# Motor_Driver2.net
KiCad netlist of a schematic drawn in Altium Designer
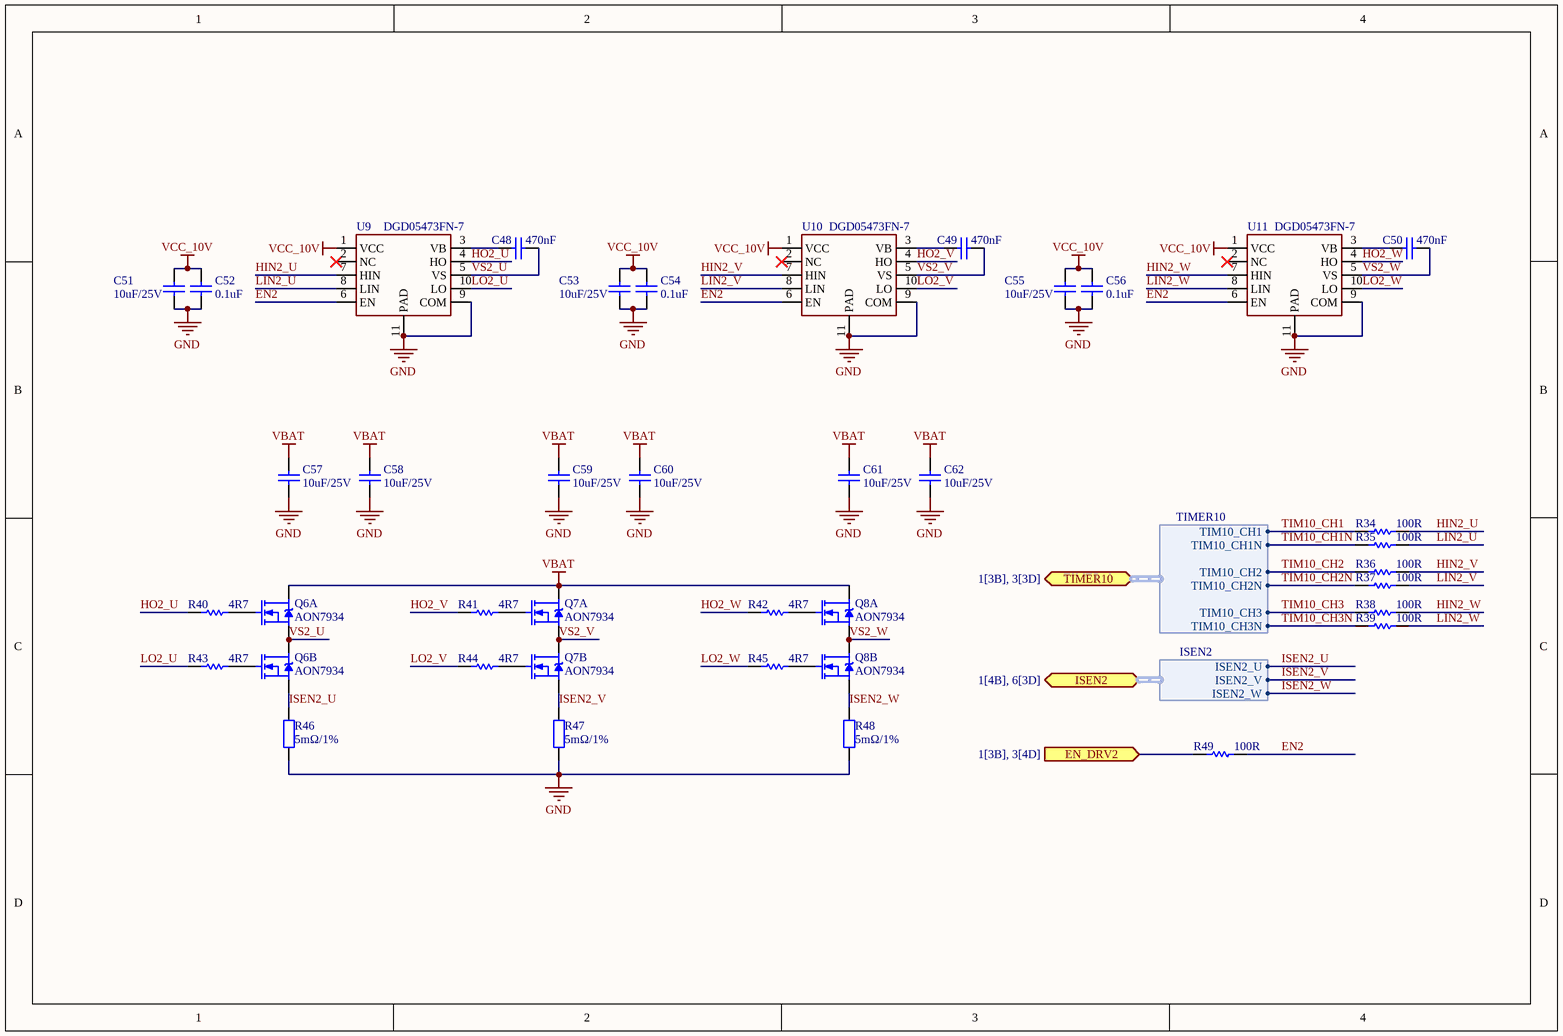
[diagram p0: Motor_Driver2.SchDoc]

(export (version "E")
  (design (tool "Eeschema 10.0.6"))
  (components
    (comp (ref "C48")
      (value "470nF")
      (footprint "C0603_NS")
      (description "Capacitor")
      (fields (field (name "PUBLISHER") "Altium Limited"))
      (libsource (lib "Miscellaneous Devices") (part "Cap"))
    )
    (comp (ref "C49")
      (value "470nF")
      (footprint "C0603_NS")
      (description "Capacitor")
      (fields (field (name "PUBLISHER") "Altium Limited"))
      (libsource (lib "Miscellaneous Devices") (part "Cap"))
    )
    (comp (ref "C50")
      (value "470nF")
      (footprint "C0603_NS")
      (description "Capacitor")
      (fields (field (name "PUBLISHER") "Altium Limited"))
      (libsource (lib "Miscellaneous Devices") (part "Cap"))
    )
    (comp (ref "C51")
      (value "10uF/25V")
      (footprint "C0603_NS")
      (description "Capacitor")
      (fields (field (name "PUBLISHER") "Altium Limited"))
      (libsource (lib "Miscellaneous Devices") (part "Cap"))
    )
    (comp (ref "C52")
      (value "0.1uF")
      (footprint "C0603_NS")
      (description "Capacitor")
      (fields (field (name "PUBLISHER") "Altium Limited"))
      (libsource (lib "Miscellaneous Devices") (part "Cap"))
    )
    (comp (ref "C53")
      (value "10uF/25V")
      (footprint "C0603_NS")
      (description "Capacitor")
      (fields (field (name "PUBLISHER") "Altium Limited"))
      (libsource (lib "Miscellaneous Devices") (part "Cap"))
    )
    (comp (ref "C54")
      (value "0.1uF")
      (footprint "C0603_NS")
      (description "Capacitor")
      (fields (field (name "PUBLISHER") "Altium Limited"))
      (libsource (lib "Miscellaneous Devices") (part "Cap"))
    )
    (comp (ref "C55")
      (value "10uF/25V")
      (footprint "C0603_NS")
      (description "Capacitor")
      (fields (field (name "PUBLISHER") "Altium Limited"))
      (libsource (lib "Miscellaneous Devices") (part "Cap"))
    )
    (comp (ref "C56")
      (value "0.1uF")
      (footprint "C0603_NS")
      (description "Capacitor")
      (fields (field (name "PUBLISHER") "Altium Limited"))
      (libsource (lib "Miscellaneous Devices") (part "Cap"))
    )
    (comp (ref "C57")
      (value "10uF/25V")
      (footprint "C0603_NS")
      (description "Capacitor")
      (libsource (lib "Miscellaneous Devices") (part "Cap"))
    )
    (comp (ref "C58")
      (value "10uF/25V")
      (footprint "C0603_NS")
      (description "Capacitor")
      (libsource (lib "Miscellaneous Devices") (part "Cap"))
    )
    (comp (ref "C59")
      (value "10uF/25V")
      (footprint "C0603_NS")
      (description "Capacitor")
      (libsource (lib "Miscellaneous Devices") (part "Cap"))
    )
    (comp (ref "C60")
      (value "10uF/25V")
      (footprint "C0603_NS")
      (description "Capacitor")
      (libsource (lib "Miscellaneous Devices") (part "Cap"))
    )
    (comp (ref "C61")
      (value "10uF/25V")
      (footprint "C0603_NS")
      (description "Capacitor")
      (libsource (lib "Miscellaneous Devices") (part "Cap"))
    )
    (comp (ref "C62")
      (value "10uF/25V")
      (footprint "C0603_NS")
      (description "Capacitor")
      (libsource (lib "Miscellaneous Devices") (part "Cap"))
    )
    (comp (ref "Q6")
      (value "AON7934")
      (footprint "POWERPAIR_3X3")
      (libsource (lib "my_library") (part "AON7934"))
    )
    (comp (ref "Q7")
      (value "AON7934")
      (footprint "POWERPAIR_3X3")
      (libsource (lib "my_library") (part "AON7934"))
    )
    (comp (ref "Q8")
      (value "AON7934")
      (footprint "POWERPAIR_3X3")
      (libsource (lib "my_library") (part "AON7934"))
    )
    (comp (ref "R34")
      (value "100R")
      (footprint "R0603_NS")
      (description "Resistor")
      (libsource (lib "Miscellaneous Devices") (part "Res1"))
    )
    (comp (ref "R35")
      (value "100R")
      (footprint "R0603_NS")
      (description "Resistor")
      (libsource (lib "Miscellaneous Devices") (part "Res1"))
    )
    (comp (ref "R36")
      (value "100R")
      (footprint "R0603_NS")
      (description "Resistor")
      (libsource (lib "Miscellaneous Devices") (part "Res1"))
    )
    (comp (ref "R37")
      (value "100R")
      (footprint "R0603_NS")
      (description "Resistor")
      (libsource (lib "Miscellaneous Devices") (part "Res1"))
    )
    (comp (ref "R38")
      (value "100R")
      (footprint "R0603_NS")
      (description "Resistor")
      (libsource (lib "Miscellaneous Devices") (part "Res1"))
    )
    (comp (ref "R39")
      (value "100R")
      (footprint "R0603_NS")
      (description "Resistor")
      (libsource (lib "Miscellaneous Devices") (part "Res1"))
    )
    (comp (ref "R40")
      (value "4R7")
      (footprint "R0603_NS")
      (description "Resistor")
      (libsource (lib "Miscellaneous Devices") (part "Res1"))
    )
    (comp (ref "R41")
      (value "4R7")
      (footprint "R0603_NS")
      (description "Resistor")
      (libsource (lib "Miscellaneous Devices") (part "Res1"))
    )
    (comp (ref "R42")
      (value "4R7")
      (footprint "R0603_NS")
      (description "Resistor")
      (libsource (lib "Miscellaneous Devices") (part "Res1"))
    )
    (comp (ref "R43")
      (value "4R7")
      (footprint "R0603_NS")
      (description "Resistor")
      (libsource (lib "Miscellaneous Devices") (part "Res1"))
    )
    (comp (ref "R44")
      (value "4R7")
      (footprint "R0603_NS")
      (description "Resistor")
      (libsource (lib "Miscellaneous Devices") (part "Res1"))
    )
    (comp (ref "R45")
      (value "4R7")
      (footprint "R0603_NS")
      (description "Resistor")
      (libsource (lib "Miscellaneous Devices") (part "Res1"))
    )
    (comp (ref "R46")
      (value "5mΩ/1%")
      (footprint "R1206_NS")
      (description "Resistor")
      (fields (field (name "PUBLISHER") "Altium Limited"))
      (libsource (lib "Miscellaneous Devices") (part "Res2"))
    )
    (comp (ref "R47")
      (value "5mΩ/1%")
      (footprint "R1206_NS")
      (description "Resistor")
      (fields (field (name "PUBLISHER") "Altium Limited"))
      (libsource (lib "Miscellaneous Devices") (part "Res2"))
    )
    (comp (ref "R48")
      (value "5mΩ/1%")
      (footprint "R1206_NS")
      (description "Resistor")
      (fields (field (name "PUBLISHER") "Altium Limited"))
      (libsource (lib "Miscellaneous Devices") (part "Res2"))
    )
    (comp (ref "R49")
      (value "100R")
      (footprint "R0603_NS")
      (description "Resistor")
      (libsource (lib "Miscellaneous Devices") (part "Res1"))
    )
    (comp (ref "U9")
      (value "DGD05473FN-7")
      (footprint "W-DFN3030-10_DGD05473")
      (libsource (lib "my_library") (part "DGD05473"))
    )
    (comp (ref "U10")
      (value "DGD05473FN-7")
      (footprint "W-DFN3030-10_DGD05473")
      (libsource (lib "my_library") (part "DGD05473"))
    )
    (comp (ref "U11")
      (value "DGD05473FN-7")
      (footprint "W-DFN3030-10_DGD05473")
      (libsource (lib "my_library") (part "DGD05473"))
    )
  )
  (nets
    (net (code "3") (name "/EN2") (class "Default")
      (node (ref "R49") (pin "2") (pinfunction "2_2") (pintype "passive"))
      (node (ref "U10") (pin "6") (pinfunction "EN_6") (pintype "passive"))
      (node (ref "U11") (pin "6") (pinfunction "EN_6") (pintype "passive"))
      (node (ref "U9") (pin "6") (pinfunction "EN_6") (pintype "passive"))
    )
    (net (code "4") (name "/EN_DRV2") (class "Default")
      (node (ref "R49") (pin "1") (pinfunction "1_1") (pintype "passive"))
    )
    (net (code "5") (name "/HIN2_U") (class "Default")
      (node (ref "R34") (pin "2") (pinfunction "2_2") (pintype "passive"))
      (node (ref "U9") (pin "7") (pinfunction "HIN_7") (pintype "passive"))
    )
    (net (code "6") (name "/HIN2_V") (class "Default")
      (node (ref "R36") (pin "2") (pinfunction "2_2") (pintype "passive"))
      (node (ref "U10") (pin "7") (pinfunction "HIN_7") (pintype "passive"))
    )
    (net (code "7") (name "/HIN2_W") (class "Default")
      (node (ref "R38") (pin "2") (pinfunction "2_2") (pintype "passive"))
      (node (ref "U11") (pin "7") (pinfunction "HIN_7") (pintype "passive"))
    )
    (net (code "8") (name "/HO2_U") (class "Default")
      (node (ref "R40") (pin "1") (pinfunction "1_1") (pintype "passive"))
      (node (ref "U9") (pin "4") (pinfunction "HO_4") (pintype "passive"))
    )
    (net (code "9") (name "/HO2_V") (class "Default")
      (node (ref "R41") (pin "1") (pinfunction "1_1") (pintype "passive"))
      (node (ref "U10") (pin "4") (pinfunction "HO_4") (pintype "passive"))
    )
    (net (code "10") (name "/HO2_W") (class "Default")
      (node (ref "R42") (pin "1") (pinfunction "1_1") (pintype "passive"))
      (node (ref "U11") (pin "4") (pinfunction "HO_4") (pintype "passive"))
    )
    (net (code "11") (name "/ISEN2_U") (class "Default")
      (node (ref "Q6") (pin "S2") (pinfunction "S2_S2") (pintype "passive"))
      (node (ref "R46") (pin "2") (pinfunction "2_2") (pintype "passive"))
    )
    (net (code "12") (name "/ISEN2_V") (class "Default")
      (node (ref "Q7") (pin "S2") (pinfunction "S2_S2") (pintype "passive"))
      (node (ref "R47") (pin "2") (pinfunction "2_2") (pintype "passive"))
    )
    (net (code "13") (name "/ISEN2_W") (class "Default")
      (node (ref "Q8") (pin "S2") (pinfunction "S2_S2") (pintype "passive"))
      (node (ref "R48") (pin "2") (pinfunction "2_2") (pintype "passive"))
    )
    (net (code "14") (name "/LIN2_U") (class "Default")
      (node (ref "R35") (pin "2") (pinfunction "2_2") (pintype "passive"))
      (node (ref "U9") (pin "8") (pinfunction "LIN_8") (pintype "passive"))
    )
    (net (code "15") (name "/LIN2_V") (class "Default")
      (node (ref "R37") (pin "2") (pinfunction "2_2") (pintype "passive"))
      (node (ref "U10") (pin "8") (pinfunction "LIN_8") (pintype "passive"))
    )
    (net (code "16") (name "/LIN2_W") (class "Default")
      (node (ref "R39") (pin "2") (pinfunction "2_2") (pintype "passive"))
      (node (ref "U11") (pin "8") (pinfunction "LIN_8") (pintype "passive"))
    )
    (net (code "17") (name "/LO2_U") (class "Default")
      (node (ref "R43") (pin "1") (pinfunction "1_1") (pintype "passive"))
      (node (ref "U9") (pin "10") (pinfunction "LO_10") (pintype "passive"))
    )
    (net (code "18") (name "/LO2_V") (class "Default")
      (node (ref "R44") (pin "1") (pinfunction "1_1") (pintype "passive"))
      (node (ref "U10") (pin "10") (pinfunction "LO_10") (pintype "passive"))
    )
    (net (code "19") (name "/LO2_W") (class "Default")
      (node (ref "R45") (pin "1") (pinfunction "1_1") (pintype "passive"))
      (node (ref "U11") (pin "10") (pinfunction "LO_10") (pintype "passive"))
    )
    (net (code "20") (name "/TIM10_CH1") (class "Default")
      (node (ref "R34") (pin "1") (pinfunction "1_1") (pintype "passive"))
    )
    (net (code "21") (name "/TIM10_CH1N") (class "Default")
      (node (ref "R35") (pin "1") (pinfunction "1_1") (pintype "passive"))
    )
    (net (code "22") (name "/TIM10_CH2") (class "Default")
      (node (ref "R36") (pin "1") (pinfunction "1_1") (pintype "passive"))
    )
    (net (code "23") (name "/TIM10_CH2N") (class "Default")
      (node (ref "R37") (pin "1") (pinfunction "1_1") (pintype "passive"))
    )
    (net (code "24") (name "/TIM10_CH3") (class "Default")
      (node (ref "R38") (pin "1") (pinfunction "1_1") (pintype "passive"))
    )
    (net (code "25") (name "/TIM10_CH3N") (class "Default")
      (node (ref "R39") (pin "1") (pinfunction "1_1") (pintype "passive"))
    )
    (net (code "26") (name "/VS2_U") (class "Default")
      (node (ref "C48") (pin "2") (pinfunction "2_2") (pintype "passive"))
      (node (ref "Q6") (pin "S1/D2") (pinfunction "S1/D2_S1/D2") (pintype "passive"))
      (node (ref "U9") (pin "5") (pinfunction "VS_5") (pintype "passive"))
    )
    (net (code "27") (name "/VS2_V") (class "Default")
      (node (ref "C49") (pin "2") (pinfunction "2_2") (pintype "passive"))
      (node (ref "Q7") (pin "S1/D2") (pinfunction "S1/D2_S1/D2") (pintype "passive"))
      (node (ref "U10") (pin "5") (pinfunction "VS_5") (pintype "passive"))
    )
    (net (code "28") (name "/VS2_W") (class "Default")
      (node (ref "C50") (pin "2") (pinfunction "2_2") (pintype "passive"))
      (node (ref "Q8") (pin "S1/D2") (pinfunction "S1/D2_S1/D2") (pintype "passive"))
      (node (ref "U11") (pin "5") (pinfunction "VS_5") (pintype "passive"))
    )
    (net (code "31") (name "GND") (class "Default")
      (node (ref "C51") (pin "2") (pinfunction "2_2") (pintype "passive"))
      (node (ref "C52") (pin "2") (pinfunction "2_2") (pintype "passive"))
      (node (ref "C53") (pin "2") (pinfunction "2_2") (pintype "passive"))
      (node (ref "C54") (pin "2") (pinfunction "2_2") (pintype "passive"))
      (node (ref "C55") (pin "2") (pinfunction "2_2") (pintype "passive"))
      (node (ref "C56") (pin "2") (pinfunction "2_2") (pintype "passive"))
      (node (ref "C57") (pin "1") (pinfunction "1_1") (pintype "passive"))
      (node (ref "C58") (pin "1") (pinfunction "1_1") (pintype "passive"))
      (node (ref "C59") (pin "1") (pinfunction "1_1") (pintype "passive"))
      (node (ref "C60") (pin "1") (pinfunction "1_1") (pintype "passive"))
      (node (ref "C61") (pin "1") (pinfunction "1_1") (pintype "passive"))
      (node (ref "C62") (pin "1") (pinfunction "1_1") (pintype "passive"))
      (node (ref "R46") (pin "1") (pinfunction "1_1") (pintype "passive"))
      (node (ref "R47") (pin "1") (pinfunction "1_1") (pintype "passive"))
      (node (ref "R48") (pin "1") (pinfunction "1_1") (pintype "passive"))
      (node (ref "U10") (pin "11") (pinfunction "PAD_11") (pintype "passive"))
      (node (ref "U10") (pin "9") (pinfunction "COM_9") (pintype "passive"))
      (node (ref "U11") (pin "11") (pinfunction "PAD_11") (pintype "passive"))
      (node (ref "U11") (pin "9") (pinfunction "COM_9") (pintype "passive"))
      (node (ref "U9") (pin "11") (pinfunction "PAD_11") (pintype "passive"))
      (node (ref "U9") (pin "9") (pinfunction "COM_9") (pintype "passive"))
    )
    (net (code "32") (name "Net-(Q6-PadG1)") (class "Default")
      (node (ref "Q6") (pin "G1") (pinfunction "G1_G1") (pintype "passive"))
      (node (ref "R40") (pin "2") (pinfunction "2_2") (pintype "passive"))
    )
    (net (code "33") (name "Net-(Q6-PadG2)") (class "Default")
      (node (ref "Q6") (pin "G2") (pinfunction "G2_G2") (pintype "passive"))
      (node (ref "R43") (pin "2") (pinfunction "2_2") (pintype "passive"))
    )
    (net (code "34") (name "Net-(Q7-PadG1)") (class "Default")
      (node (ref "Q7") (pin "G1") (pinfunction "G1_G1") (pintype "passive"))
      (node (ref "R41") (pin "2") (pinfunction "2_2") (pintype "passive"))
    )
    (net (code "35") (name "Net-(Q7-PadG2)") (class "Default")
      (node (ref "Q7") (pin "G2") (pinfunction "G2_G2") (pintype "passive"))
      (node (ref "R44") (pin "2") (pinfunction "2_2") (pintype "passive"))
    )
    (net (code "36") (name "Net-(Q8-PadG1)") (class "Default")
      (node (ref "Q8") (pin "G1") (pinfunction "G1_G1") (pintype "passive"))
      (node (ref "R42") (pin "2") (pinfunction "2_2") (pintype "passive"))
    )
    (net (code "37") (name "Net-(Q8-PadG2)") (class "Default")
      (node (ref "Q8") (pin "G2") (pinfunction "G2_G2") (pintype "passive"))
      (node (ref "R45") (pin "2") (pinfunction "2_2") (pintype "passive"))
    )
    (net (code "38") (name "Net-(U9-VB)") (class "Default")
      (node (ref "C48") (pin "1") (pinfunction "1_1") (pintype "passive"))
      (node (ref "U9") (pin "3") (pinfunction "VB_3") (pintype "passive"))
    )
    (net (code "39") (name "Net-(U10-VB)") (class "Default")
      (node (ref "C49") (pin "1") (pinfunction "1_1") (pintype "passive"))
      (node (ref "U10") (pin "3") (pinfunction "VB_3") (pintype "passive"))
    )
    (net (code "40") (name "Net-(U11-VB)") (class "Default")
      (node (ref "C50") (pin "1") (pinfunction "1_1") (pintype "passive"))
      (node (ref "U11") (pin "3") (pinfunction "VB_3") (pintype "passive"))
    )
    (net (code "41") (name "VBAT") (class "Default")
      (node (ref "C57") (pin "2") (pinfunction "2_2") (pintype "passive"))
      (node (ref "C58") (pin "2") (pinfunction "2_2") (pintype "passive"))
      (node (ref "C59") (pin "2") (pinfunction "2_2") (pintype "passive"))
      (node (ref "C60") (pin "2") (pinfunction "2_2") (pintype "passive"))
      (node (ref "C61") (pin "2") (pinfunction "2_2") (pintype "passive"))
      (node (ref "C62") (pin "2") (pinfunction "2_2") (pintype "passive"))
      (node (ref "Q6") (pin "D1") (pinfunction "D1_D1") (pintype "passive"))
      (node (ref "Q7") (pin "D1") (pinfunction "D1_D1") (pintype "passive"))
      (node (ref "Q8") (pin "D1") (pinfunction "D1_D1") (pintype "passive"))
    )
    (net (code "42") (name "VCC_10V") (class "Default")
      (node (ref "C51") (pin "1") (pinfunction "1_1") (pintype "passive"))
      (node (ref "C52") (pin "1") (pinfunction "1_1") (pintype "passive"))
      (node (ref "C53") (pin "1") (pinfunction "1_1") (pintype "passive"))
      (node (ref "C54") (pin "1") (pinfunction "1_1") (pintype "passive"))
      (node (ref "C55") (pin "1") (pinfunction "1_1") (pintype "passive"))
      (node (ref "C56") (pin "1") (pinfunction "1_1") (pintype "passive"))
      (node (ref "U10") (pin "1") (pinfunction "VCC_1") (pintype "passive"))
      (node (ref "U11") (pin "1") (pinfunction "VCC_1") (pintype "passive"))
      (node (ref "U9") (pin "1") (pinfunction "VCC_1") (pintype "passive"))
    )
    (net (code "43") (name "unconnected-(U9-NC-Pad2)") (class "Default")
      (node (ref "U9") (pin "2") (pinfunction "NC_2") (pintype "passive+no_connect"))
    )
    (net (code "44") (name "unconnected-(U10-NC-Pad2)") (class "Default")
      (node (ref "U10") (pin "2") (pinfunction "NC_2") (pintype "passive+no_connect"))
    )
    (net (code "45") (name "unconnected-(U11-NC-Pad2)") (class "Default")
      (node (ref "U11") (pin "2") (pinfunction "NC_2") (pintype "passive+no_connect"))
    )
  )
)
